# LeadAcid_Battery_Charger_v001.net
KiCad netlist of a schematic drawn in EAGLE
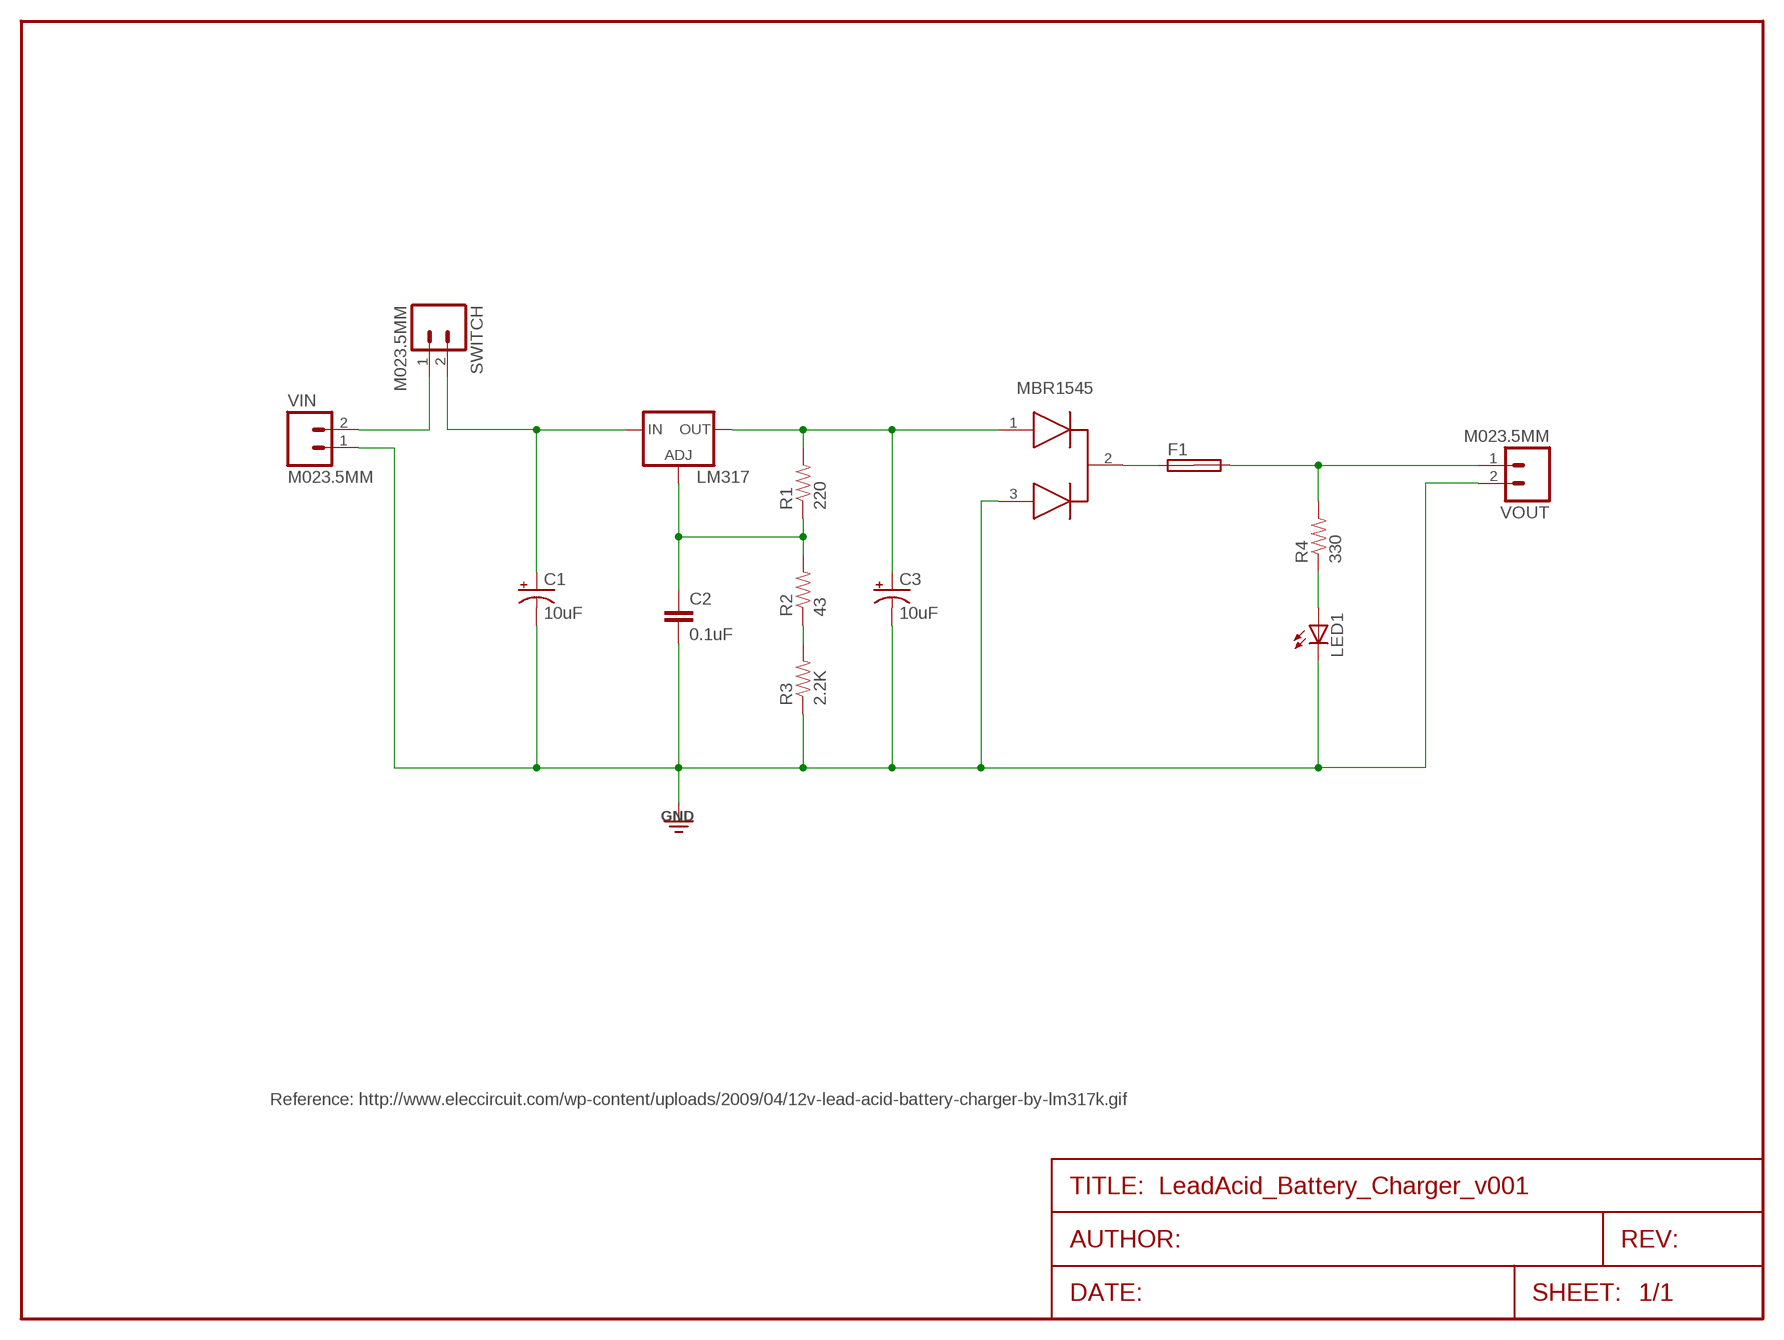
[diagram p0: schematic, sheet 1]

(export (version "E")
  (design (tool "Eeschema 10.0.6"))
  (components
    (comp (ref "C1")
      (value "10uF")
      (footprint "eagle-import:CPOL-RADIAL-10UF-25V")
      (libsource (lib "eagle-import") (part "CAP_POLPTH2"))
    )
    (comp (ref "C2")
      (value "0.1uF")
      (footprint "eagle-import:CAP-PTH-5MM")
      (libsource (lib "eagle-import") (part "CAPPTH1"))
    )
    (comp (ref "C3")
      (value "10uF")
      (footprint "eagle-import:CPOL-RADIAL-10UF-25V")
      (libsource (lib "eagle-import") (part "CAP_POLPTH2"))
    )
    (comp (ref "F1")
      (value "SHK20L")
      (footprint "eagle-import:SHK20L")
      (libsource (lib "eagle-import") (part "SHK20L"))
    )
    (comp (ref "LED1")
      (value "LED3MM")
      (footprint "eagle-import:LED3MM")
      (libsource (lib "eagle-import") (part "LED3MM"))
    )
    (comp (ref "LM317")
      (value "LM317TS")
      (footprint "eagle-import:317TS")
      (libsource (lib "eagle-import") (part "LM317TS"))
    )
    (comp (ref "MBR1545")
      (value "MBR1545")
      (footprint "eagle-import:TO-220")
      (libsource (lib "eagle-import") (part "MBR1545"))
    )
    (comp (ref "R1")
      (value "220")
      (footprint "eagle-import:AXIAL-0.4")
      (libsource (lib "eagle-import") (part "RESISTORPTH-1/4W"))
    )
    (comp (ref "R2")
      (value "43")
      (footprint "eagle-import:AXIAL-0.4")
      (libsource (lib "eagle-import") (part "RESISTORPTH-1/4W"))
    )
    (comp (ref "R3")
      (value "2.2K")
      (footprint "eagle-import:AXIAL-0.4")
      (libsource (lib "eagle-import") (part "RESISTORPTH-1/4W"))
    )
    (comp (ref "R4")
      (value "330")
      (footprint "eagle-import:AXIAL-0.4")
      (libsource (lib "eagle-import") (part "RESISTORPTH-1/4W"))
    )
    (comp (ref "SWITCH")
      (value "M023.5MM")
      (footprint "eagle-import:SCREWTERMINAL-3.5MM-2")
      (libsource (lib "eagle-import") (part "M023.5MM"))
    )
    (comp (ref "VIN")
      (value "M023.5MM")
      (footprint "eagle-import:SCREWTERMINAL-3.5MM-2")
      (libsource (lib "eagle-import") (part "M023.5MM"))
    )
    (comp (ref "VOUT")
      (value "M023.5MM")
      (footprint "eagle-import:SCREWTERMINAL-3.5MM-2")
      (libsource (lib "eagle-import") (part "M023.5MM"))
    )
  )
  (nets
    (net (code "1") (name "GND") (class "Default")
      (node (ref "C1") (pin "2") (pinfunction "-_2") (pintype "passive"))
      (node (ref "C2") (pin "2") (pinfunction "2_2") (pintype "passive"))
      (node (ref "C3") (pin "2") (pinfunction "-_2") (pintype "passive"))
      (node (ref "LED1") (pin "K") (pinfunction "C_K") (pintype "passive"))
      (node (ref "MBR1545") (pin "3") (pinfunction "P$3_3") (pintype "bidirectional"))
      (node (ref "R3") (pin "P$1") (pinfunction "1_P$1") (pintype "passive"))
      (node (ref "VIN") (pin "1") (pinfunction "1_1") (pintype "passive"))
      (node (ref "VOUT") (pin "2") (pinfunction "2_2") (pintype "passive"))
    )
    (net (code "2") (name "Net-(C1-+)") (class "Default")
      (node (ref "C1") (pin "1") (pinfunction "+_1") (pintype "passive"))
      (node (ref "LM317") (pin "3") (pinfunction "IN_3") (pintype "input"))
      (node (ref "SWITCH") (pin "2") (pinfunction "2_2") (pintype "passive"))
    )
    (net (code "3") (name "Net-(C3-+)") (class "Default")
      (node (ref "C3") (pin "1") (pinfunction "+_1") (pintype "passive"))
      (node (ref "LM317") (pin "2") (pinfunction "OUT_2") (pintype "passive"))
      (node (ref "MBR1545") (pin "1") (pinfunction "P$1_1") (pintype "bidirectional"))
      (node (ref "R1") (pin "P$2") (pinfunction "2_P$2") (pintype "passive"))
    )
    (net (code "4") (name "Net-(LM317-ADJ)") (class "Default")
      (node (ref "C2") (pin "1") (pinfunction "1_1") (pintype "passive"))
      (node (ref "LM317") (pin "1") (pinfunction "ADJ_1") (pintype "input"))
      (node (ref "R1") (pin "P$1") (pinfunction "1_P$1") (pintype "passive"))
      (node (ref "R2") (pin "P$2") (pinfunction "2_P$2") (pintype "passive"))
    )
    (net (code "5") (name "Net-(MBR1545-P$2)") (class "Default")
      (node (ref "F1") (pin "1A") (pinfunction "1A_1A") (pintype "passive"))
      (node (ref "MBR1545") (pin "2") (pinfunction "P$2_2") (pintype "bidirectional"))
    )
    (net (code "6") (name "Net-(R2-1)") (class "Default")
      (node (ref "R2") (pin "P$1") (pinfunction "1_P$1") (pintype "passive"))
      (node (ref "R3") (pin "P$2") (pinfunction "2_P$2") (pintype "passive"))
    )
    (net (code "7") (name "Net-(R4-1)") (class "Default")
      (node (ref "LED1") (pin "A") (pinfunction "A_A") (pintype "passive"))
      (node (ref "R4") (pin "P$1") (pinfunction "1_P$1") (pintype "passive"))
    )
    (net (code "8") (name "Net-(R4-2)") (class "Default")
      (node (ref "F1") (pin "2A") (pinfunction "2A_2A") (pintype "passive"))
      (node (ref "R4") (pin "P$2") (pinfunction "2_P$2") (pintype "passive"))
      (node (ref "VOUT") (pin "1") (pinfunction "1_1") (pintype "passive"))
    )
    (net (code "9") (name "Net-(SWITCH-Pad1)") (class "Default")
      (node (ref "SWITCH") (pin "1") (pinfunction "1_1") (pintype "passive"))
      (node (ref "VIN") (pin "2") (pinfunction "2_2") (pintype "passive"))
    )
    (net (code "10") (name "unconnected-(F1-Pad1B)") (class "Default")
      (node (ref "F1") (pin "1B") (pinfunction "1B_1B") (pintype "passive"))
    )
    (net (code "11") (name "unconnected-(F1-Pad2B)") (class "Default")
      (node (ref "F1") (pin "2B") (pinfunction "2B_2B") (pintype "passive"))
    )
  )
)
